# USB_OTG_HS.net
KiCad netlist of a schematic drawn in Altium Designer
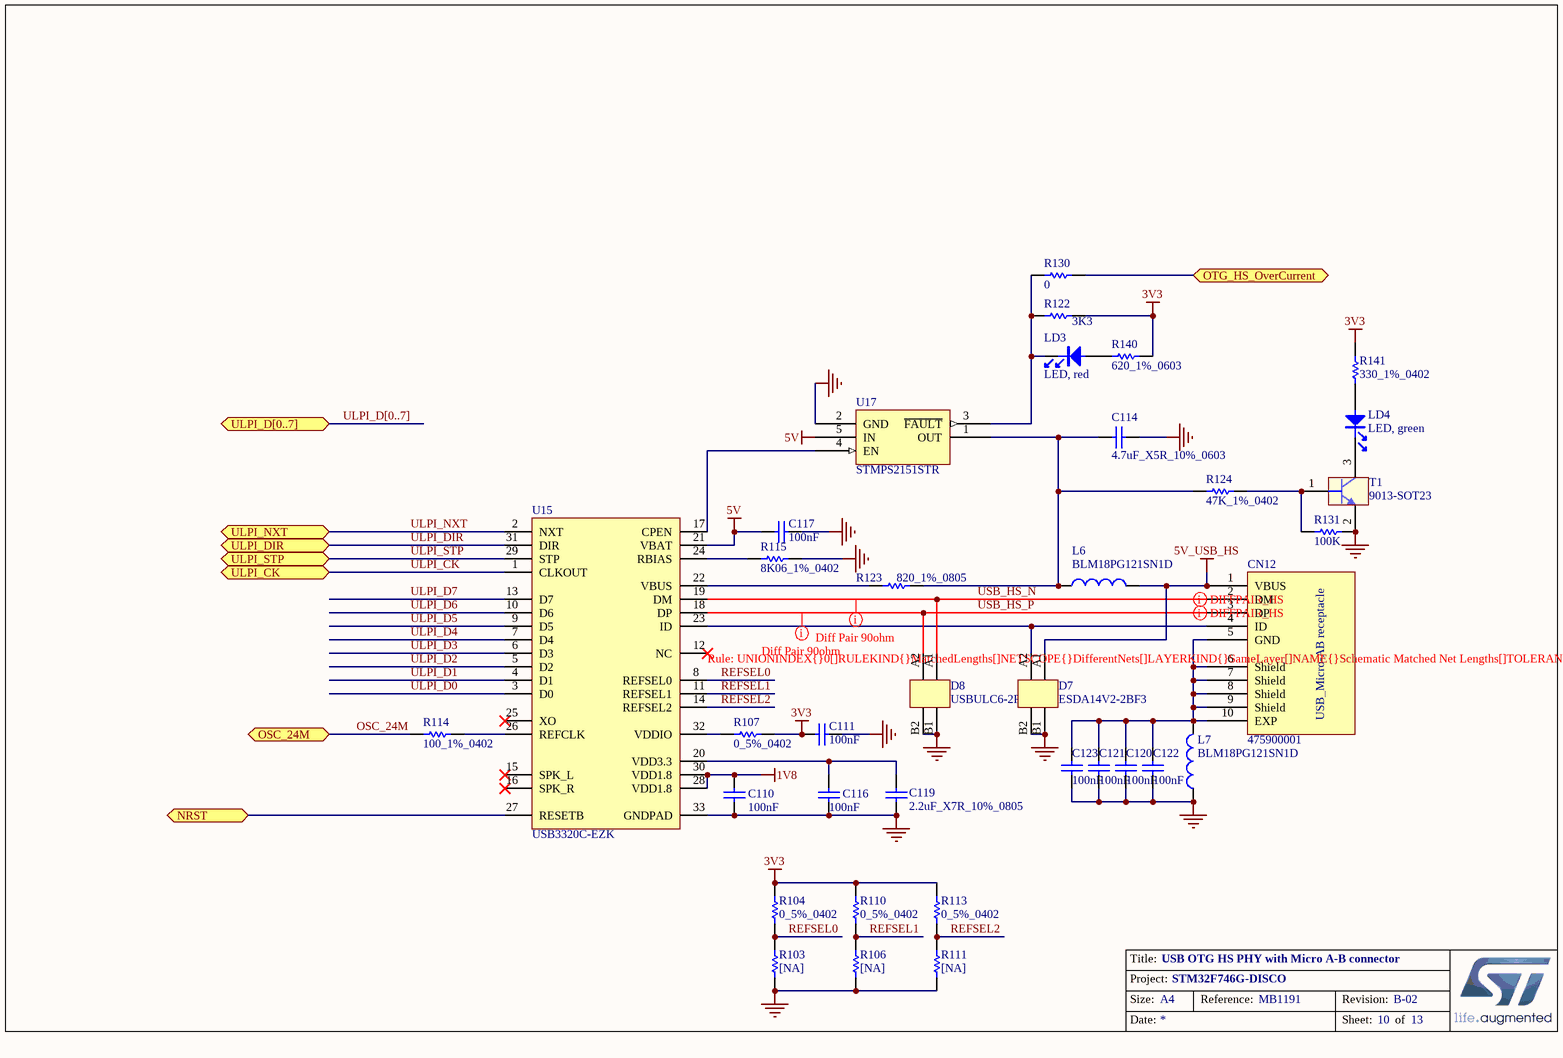
[diagram p0: USB_OTG_HS.SchDoc]

(export (version "E")
  (design (tool "Eeschema 10.0.6"))
  (components
    (comp (ref "C110")
      (value "100nF")
      (footprint "0402C")
      (description "Capacitor,100nF,16V,X7R,10%,0402,YAGEO")
      (libsource (lib "MCD_TOOLS") (part "Cap_100nF_X7R_10%_0402"))
    )
    (comp (ref "C111")
      (value "100nF")
      (footprint "0402C")
      (description "Capacitor,100nF,16V,X7R,10%,0402,YAGEO")
      (libsource (lib "MCD_TOOLS") (part "Cap_100nF_X7R_10%_0402"))
    )
    (comp (ref "C114")
      (value "4.7uF_X5R_10%_0603")
      (footprint "0603C")
      (description "Capacitor,4.7uF,16V, X5R,10%,0603,YAGEO")
      (libsource (lib "MCD_TOOLS") (part "Cap_4.7uF_X5R_10%_0603"))
    )
    (comp (ref "C116")
      (value "100nF")
      (footprint "0402C")
      (description "Capacitor,100nF,16V,X7R,10%,0402,YAGEO")
      (libsource (lib "MCD_TOOLS") (part "Cap_100nF_X7R_10%_0402"))
    )
    (comp (ref "C117")
      (value "100nF")
      (footprint "0402C")
      (description "Capacitor,100nF,16V,X7R,10%,0402,YAGEO")
      (libsource (lib "MCD_TOOLS") (part "Cap_100nF_X7R_10%_0402"))
    )
    (comp (ref "C119")
      (value "2.2uF_X7R_10%_0805")
      (footprint "TAN-A")
      (description "Capacitor,2.2uF,16V, X7R,10%,0805,YAGEO")
      (libsource (lib "MCD_TOOLS") (part "Cap_2.2uF_X7R_10%_0805"))
    )
    (comp (ref "C120")
      (value "100nF")
      (footprint "0402C")
      (description "Capacitor,100nF,16V,X7R,10%,0402,YAGEO")
      (libsource (lib "MCD_TOOLS") (part "Cap_100nF_X7R_10%_0402"))
    )
    (comp (ref "C121")
      (value "100nF")
      (footprint "0402C")
      (description "Capacitor,100nF,16V,X7R,10%,0402,YAGEO")
      (libsource (lib "MCD_TOOLS") (part "Cap_100nF_X7R_10%_0402"))
    )
    (comp (ref "C122")
      (value "100nF")
      (footprint "0402C")
      (description "Capacitor,100nF,16V,X7R,10%,0402,YAGEO")
      (libsource (lib "MCD_TOOLS") (part "Cap_100nF_X7R_10%_0402"))
    )
    (comp (ref "C123")
      (value "100nF")
      (footprint "0402C")
      (description "Capacitor,100nF,16V,X7R,10%,0402,YAGEO")
      (libsource (lib "MCD_TOOLS") (part "Cap_100nF_X7R_10%_0402"))
    )
    (comp (ref "CN12")
      (value "475900001")
      (footprint "USB-MICRO-AB")
      (description "USB-MICRO-AB, 47590-0001, SMT, MOLEX")
      (libsource (lib "MCD_TOOLS") (part "475900001"))
    )
    (comp (ref "D7")
      (value "ESDA14V2-2BF3")
      (footprint "BGA4_1X1")
      (description "Quad bidirectional Transil array for ESD protection")
      (libsource (lib "MCD_TOOLS") (part "ESDA14V2-2BF3"))
    )
    (comp (ref "D8")
      (value "USBULC6-2F3")
      (footprint "BGA4_1X1")
      (description "2-line Transil, (TVS), ultralow capacitance protection for high speed USB")
      (libsource (lib "MCD_TOOLS") (part "USBULC6-2F3"))
    )
    (comp (ref "L6")
      (value "BLM18PG121SN1D")
      (footprint "0603L")
      (description "Bead,120R,2A,0603,BLM18PG121SN1D,MURATA")
      (libsource (lib "MCD_TOOLS") (part "BEAD_120R_2A_0603"))
    )
    (comp (ref "L7")
      (value "BLM18PG121SN1D")
      (footprint "0603L")
      (description "Bead,120R,2A,0603,BLM18PG121SN1D,MURATA")
      (libsource (lib "MCD_TOOLS") (part "BEAD_120R_2A_0603"))
    )
    (comp (ref "LD3")
      (value "LED, red")
      (footprint "0603D")
      (description "LED,red,0603,19-213-R6C-AP1Q2B/3T,everlight")
      (libsource (lib "MCD_TOOLS") (part "LED_red"))
    )
    (comp (ref "LD4")
      (value "LED, green")
      (footprint "0603D")
      (description "LED,green,0603,19-213SYGC/S530-E2/TR8,everlight")
      (libsource (lib "MCD_TOOLS") (part "LED_green"))
    )
    (comp (ref "R103")
      (value "[NA]")
      (footprint "0402R")
      (description "Resistor,[NA],0402")
      (libsource (lib "MCD_TOOLS") (part "Res_NA_0402"))
    )
    (comp (ref "R104")
      (value "0_5%_0402")
      (footprint "0402R")
      (description "Resistor,0,0402,5%,YAGEO")
      (libsource (lib "MCD_TOOLS") (part "Res_0_5%_0402"))
    )
    (comp (ref "R106")
      (value "[NA]")
      (footprint "0402R")
      (description "Resistor,[NA],0402")
      (libsource (lib "MCD_TOOLS") (part "Res_NA_0402"))
    )
    (comp (ref "R107")
      (value "0_5%_0402")
      (footprint "0402R")
      (description "Resistor,0,0402,5%,YAGEO")
      (libsource (lib "MCD_TOOLS") (part "Res_0_5%_0402"))
    )
    (comp (ref "R110")
      (value "0_5%_0402")
      (footprint "0402R")
      (description "Resistor,0,0402,5%,YAGEO")
      (libsource (lib "MCD_TOOLS") (part "Res_0_5%_0402"))
    )
    (comp (ref "R111")
      (value "[NA]")
      (footprint "0402R")
      (description "Resistor,[NA],0402")
      (libsource (lib "MCD_TOOLS") (part "Res_NA_0402"))
    )
    (comp (ref "R113")
      (value "0_5%_0402")
      (footprint "0402R")
      (description "Resistor,0,0402,5%,YAGEO")
      (libsource (lib "MCD_TOOLS") (part "Res_0_5%_0402"))
    )
    (comp (ref "R114")
      (value "100_1%_0402")
      (footprint "0402R")
      (description "Resistor,100,0402,1%,YAGEO")
      (libsource (lib "MCD_TOOLS") (part "Res_100_1%_0402"))
    )
    (comp (ref "R115")
      (value "8K06_1%_0402")
      (footprint "0402R")
      (description "Resistor,8K06,0402,1%,YAGEO")
      (libsource (lib "MCD_TOOLS") (part "Res_8K06_1%_0402"))
    )
    (comp (ref "R122")
      (value "3K3")
      (footprint "0402R")
      (description "Resistor,3K3,0402,1%,YAGEO")
      (libsource (lib "MCD_TOOLS") (part "Res_3K3_1%_0402"))
    )
    (comp (ref "R123")
      (value "820_1%_0805")
      (footprint "0805R")
      (description "Resistor,820,0805,1%,YAGEO")
      (libsource (lib "MCD_TOOLS") (part "Res_820_1%_0805"))
    )
    (comp (ref "R124")
      (value "47K_1%_0402")
      (footprint "0402R")
      (description "Resistor,47K,0402,1%,YAGEO")
      (libsource (lib "MCD_TOOLS") (part "Res_47K_1%_0402"))
    )
    (comp (ref "R130")
      (value "0")
      (footprint "0402R")
      (description "Resistor,0,0402,5%,YAGEO")
      (libsource (lib "MCD_TOOLS") (part "Res_0_5%_0402"))
    )
    (comp (ref "R131")
      (value "100K")
      (footprint "0402R")
      (description "Resistor,100K,0402,1%,YAGEO")
      (libsource (lib "MCD_TOOLS") (part "Res_100K_1%_0402"))
    )
    (comp (ref "R140")
      (value "620_1%_0603")
      (footprint "0603R")
      (description "Resistor,620,0603,1%,VISHAY")
      (libsource (lib "MCD_TOOLS") (part "Res_620_1%_0603"))
    )
    (comp (ref "R141")
      (value "330_1%_0402")
      (footprint "0402R")
      (description "Resistor,330,0402,1%,YAGEO")
      (libsource (lib "MCD_TOOLS") (part "Res_330_1%_0402"))
    )
    (comp (ref "T1")
      (value "9013-SOT23")
      (footprint "SOT23")
      (description "NPN Bipolar Transistor, SOT-23 Footprint")
      (libsource (lib "MCD_TOOLS") (part "9013-SOT23"))
    )
    (comp (ref "U15")
      (value "USB3320C-EZK")
      (footprint "QFN32_0R5_5X5")
      (description "USB3320C, Hi-Speed USB Host, Device or OTG PHY with ULPI Low Pin Interface")
      (libsource (lib "MCD_TOOLS") (part "USB3320C-EZK"))
    )
    (comp (ref "U17")
      (value "STMPS2151STR")
      (footprint "SOT23-5L")
      (description "Enhanced single channel power switches")
      (libsource (lib "MCD_TOOLS") (part "STMPS2151STR"))
    )
  )
  (nets
    (net (code "1") (name "/NRST") (class "Default")
      (node (ref "U15") (pin "27") (pinfunction "RESETB_27") (pintype "passive"))
    )
    (net (code "2") (name "/OSC_24M") (class "Default")
      (node (ref "R114") (pin "1") (pinfunction "1_1") (pintype "passive"))
    )
    (net (code "3") (name "/OTG_HS_OverCurrent") (class "Default")
      (node (ref "R130") (pin "2") (pinfunction "2_2") (pintype "passive"))
    )
    (net (code "4") (name "/REFSEL0") (class "Default")
      (node (ref "R103") (pin "2") (pinfunction "2_2") (pintype "passive"))
      (node (ref "R104") (pin "1") (pinfunction "1_1") (pintype "passive"))
      (node (ref "U15") (pin "8") (pinfunction "REFSEL0_8") (pintype "passive"))
    )
    (net (code "5") (name "/REFSEL1") (class "Default")
      (node (ref "R106") (pin "2") (pinfunction "2_2") (pintype "passive"))
      (node (ref "R110") (pin "1") (pinfunction "1_1") (pintype "passive"))
      (node (ref "U15") (pin "11") (pinfunction "REFSEL1_11") (pintype "passive"))
    )
    (net (code "6") (name "/REFSEL2") (class "Default")
      (node (ref "R111") (pin "2") (pinfunction "2_2") (pintype "passive"))
      (node (ref "R113") (pin "1") (pinfunction "1_1") (pintype "passive"))
      (node (ref "U15") (pin "14") (pinfunction "REFSEL2_14") (pintype "passive"))
    )
    (net (code "7") (name "/ULPI_CK") (class "Default")
      (node (ref "U15") (pin "1") (pinfunction "CLKOUT_1") (pintype "passive"))
    )
    (net (code "8") (name "/ULPI_D0") (class "Default")
      (node (ref "U15") (pin "3") (pinfunction "D0_3") (pintype "passive"))
    )
    (net (code "9") (name "/ULPI_D1") (class "Default")
      (node (ref "U15") (pin "4") (pinfunction "D1_4") (pintype "passive"))
    )
    (net (code "10") (name "/ULPI_D2") (class "Default")
      (node (ref "U15") (pin "5") (pinfunction "D2_5") (pintype "passive"))
    )
    (net (code "11") (name "/ULPI_D3") (class "Default")
      (node (ref "U15") (pin "6") (pinfunction "D3_6") (pintype "passive"))
    )
    (net (code "12") (name "/ULPI_D4") (class "Default")
      (node (ref "U15") (pin "7") (pinfunction "D4_7") (pintype "passive"))
    )
    (net (code "13") (name "/ULPI_D5") (class "Default")
      (node (ref "U15") (pin "9") (pinfunction "D5_9") (pintype "passive"))
    )
    (net (code "14") (name "/ULPI_D6") (class "Default")
      (node (ref "U15") (pin "10") (pinfunction "D6_10") (pintype "passive"))
    )
    (net (code "15") (name "/ULPI_D7") (class "Default")
      (node (ref "U15") (pin "13") (pinfunction "D7_13") (pintype "passive"))
    )
    (net (code "16") (name "/ULPI_DIR") (class "Default")
      (node (ref "U15") (pin "31") (pinfunction "DIR_31") (pintype "passive"))
    )
    (net (code "18") (name "/ULPI_NXT") (class "Default")
      (node (ref "U15") (pin "2") (pinfunction "NXT_2") (pintype "passive"))
    )
    (net (code "19") (name "/ULPI_STP") (class "Default")
      (node (ref "U15") (pin "29") (pinfunction "STP_29") (pintype "passive"))
    )
    (net (code "20") (name "/USB_HS_N") (class "Default")
      (node (ref "CN12") (pin "2") (pinfunction "DM_2") (pintype "passive"))
      (node (ref "D8") (pin "A1") (pintype "passive"))
      (node (ref "U15") (pin "19") (pinfunction "DM_19") (pintype "passive"))
    )
    (net (code "21") (name "/USB_HS_P") (class "Default")
      (node (ref "CN12") (pin "3") (pinfunction "DP_3") (pintype "passive"))
      (node (ref "D8") (pin "A2") (pintype "passive"))
      (node (ref "U15") (pin "18") (pinfunction "DP_18") (pintype "passive"))
    )
    (net (code "22") (name "1V8") (class "Default")
      (node (ref "C110") (pin "2") (pinfunction "2_2") (pintype "passive"))
      (node (ref "U15") (pin "28") (pinfunction "VDD1.8_28") (pintype "passive"))
      (node (ref "U15") (pin "30") (pinfunction "VDD1.8_30") (pintype "passive"))
    )
    (net (code "23") (name "3V3") (class "Default")
      (node (ref "C111") (pin "1") (pinfunction "1_1") (pintype "passive"))
      (node (ref "R104") (pin "2") (pinfunction "2_2") (pintype "passive"))
      (node (ref "R107") (pin "2") (pinfunction "2_2") (pintype "passive"))
      (node (ref "R110") (pin "2") (pinfunction "2_2") (pintype "passive"))
      (node (ref "R113") (pin "2") (pinfunction "2_2") (pintype "passive"))
      (node (ref "R122") (pin "1") (pinfunction "1_1") (pintype "passive"))
      (node (ref "R140") (pin "2") (pinfunction "2_2") (pintype "passive"))
      (node (ref "R141") (pin "2") (pinfunction "2_2") (pintype "passive"))
    )
    (net (code "24") (name "5V") (class "Default")
      (node (ref "C117") (pin "1") (pinfunction "1_1") (pintype "passive"))
      (node (ref "U15") (pin "21") (pinfunction "VBAT_21") (pintype "passive"))
      (node (ref "U17") (pin "5") (pinfunction "IN_5") (pintype "passive"))
    )
    (net (code "25") (name "5V_USB_HS") (class "Default")
      (node (ref "CN12") (pin "1") (pinfunction "VBUS_1") (pintype "passive"))
      (node (ref "D7") (pin "A1") (pintype "passive"))
      (node (ref "L6") (pin "2") (pinfunction "2_2") (pintype "passive"))
    )
    (net (code "26") (name "GND") (class "Default")
      (node (ref "C110") (pin "1") (pinfunction "1_1") (pintype "passive"))
      (node (ref "C111") (pin "2") (pinfunction "2_2") (pintype "passive"))
      (node (ref "C114") (pin "2") (pinfunction "2_2") (pintype "passive"))
      (node (ref "C116") (pin "1") (pinfunction "1_1") (pintype "passive"))
      (node (ref "C117") (pin "2") (pinfunction "2_2") (pintype "passive"))
      (node (ref "C119") (pin "1") (pinfunction "1_1") (pintype "passive"))
      (node (ref "C120") (pin "1") (pinfunction "1_1") (pintype "passive"))
      (node (ref "C121") (pin "1") (pinfunction "1_1") (pintype "passive"))
      (node (ref "C122") (pin "1") (pinfunction "1_1") (pintype "passive"))
      (node (ref "C123") (pin "1") (pinfunction "1_1") (pintype "passive"))
      (node (ref "D7") (pin "B1") (pintype "passive"))
      (node (ref "D7") (pin "B2") (pintype "passive"))
      (node (ref "D8") (pin "B1") (pintype "passive"))
      (node (ref "D8") (pin "B2") (pintype "passive"))
      (node (ref "L7") (pin "1") (pinfunction "1_1") (pintype "passive"))
      (node (ref "R103") (pin "1") (pinfunction "1_1") (pintype "passive"))
      (node (ref "R106") (pin "1") (pinfunction "1_1") (pintype "passive"))
      (node (ref "R111") (pin "1") (pinfunction "1_1") (pintype "passive"))
      (node (ref "R115") (pin "2") (pinfunction "2_2") (pintype "passive"))
      (node (ref "R131") (pin "2") (pinfunction "2_2") (pintype "passive"))
      (node (ref "T1") (pin "2") (pinfunction "E_2") (pintype "passive"))
      (node (ref "U15") (pin "33") (pinfunction "GNDPAD_33") (pintype "passive"))
      (node (ref "U17") (pin "2") (pinfunction "GND_2") (pintype "passive"))
    )
    (net (code "27") (name "Net-(CN12-EXP)") (class "Default")
      (node (ref "C120") (pin "2") (pinfunction "2_2") (pintype "passive"))
      (node (ref "C121") (pin "2") (pinfunction "2_2") (pintype "passive"))
      (node (ref "C122") (pin "2") (pinfunction "2_2") (pintype "passive"))
      (node (ref "C123") (pin "2") (pinfunction "2_2") (pintype "passive"))
      (node (ref "CN12") (pin "10") (pinfunction "EXP_10") (pintype "passive"))
      (node (ref "CN12") (pin "5") (pinfunction "GND_5") (pintype "passive"))
      (node (ref "CN12") (pin "6") (pinfunction "Shield_6") (pintype "passive"))
      (node (ref "CN12") (pin "7") (pinfunction "Shield_7") (pintype "passive"))
      (node (ref "CN12") (pin "8") (pinfunction "Shield_8") (pintype "passive"))
      (node (ref "CN12") (pin "9") (pinfunction "Shield_9") (pintype "passive"))
      (node (ref "L7") (pin "2") (pinfunction "2_2") (pintype "passive"))
    )
    (net (code "28") (name "Net-(CN12-ID)") (class "Default")
      (node (ref "CN12") (pin "4") (pinfunction "ID_4") (pintype "passive"))
      (node (ref "D7") (pin "A2") (pintype "passive"))
      (node (ref "U15") (pin "23") (pinfunction "ID_23") (pintype "passive"))
    )
    (net (code "29") (name "Net-(LD3-Pad1)") (class "Default")
      (node (ref "LD3") (pin "1") (pintype "passive"))
      (node (ref "R140") (pin "1") (pinfunction "1_1") (pintype "passive"))
    )
    (net (code "30") (name "Net-(LD4-Pad1)") (class "Default")
      (node (ref "LD4") (pin "1") (pintype "passive"))
      (node (ref "R141") (pin "1") (pinfunction "1_1") (pintype "passive"))
    )
    (net (code "31") (name "Net-(T1-B)") (class "Default")
      (node (ref "R124") (pin "2") (pinfunction "2_2") (pintype "passive"))
      (node (ref "R131") (pin "1") (pinfunction "1_1") (pintype "passive"))
      (node (ref "T1") (pin "1") (pinfunction "B_1") (pintype "passive"))
    )
    (net (code "32") (name "Net-(T1-C)") (class "Default")
      (node (ref "LD4") (pin "2") (pintype "passive"))
      (node (ref "T1") (pin "3") (pinfunction "C_3") (pintype "passive"))
    )
    (net (code "33") (name "Net-(U15-CPEN)") (class "Default")
      (node (ref "U15") (pin "17") (pinfunction "CPEN_17") (pintype "passive"))
      (node (ref "U17") (pin "4") (pinfunction "EN_4") (pintype "input"))
    )
    (net (code "34") (name "Net-(U15-RBIAS)") (class "Default")
      (node (ref "R115") (pin "1") (pinfunction "1_1") (pintype "passive"))
      (node (ref "U15") (pin "24") (pinfunction "RBIAS_24") (pintype "passive"))
    )
    (net (code "35") (name "Net-(U15-REFCLK)") (class "Default")
      (node (ref "R114") (pin "2") (pinfunction "2_2") (pintype "passive"))
      (node (ref "U15") (pin "26") (pinfunction "REFCLK_26") (pintype "passive"))
    )
    (net (code "36") (name "Net-(U15-VBUS)") (class "Default")
      (node (ref "R123") (pin "1") (pinfunction "1_1") (pintype "passive"))
      (node (ref "U15") (pin "22") (pinfunction "VBUS_22") (pintype "passive"))
    )
    (net (code "37") (name "Net-(U15-VDD3.3)") (class "Default")
      (node (ref "C116") (pin "2") (pinfunction "2_2") (pintype "passive"))
      (node (ref "C119") (pin "2") (pinfunction "2_2") (pintype "passive"))
      (node (ref "U15") (pin "20") (pinfunction "VDD3.3_20") (pintype "passive"))
    )
    (net (code "38") (name "Net-(U15-VDDIO)") (class "Default")
      (node (ref "R107") (pin "1") (pinfunction "1_1") (pintype "passive"))
      (node (ref "U15") (pin "32") (pinfunction "VDDIO_32") (pintype "passive"))
    )
    (net (code "39") (name "Net-(U17-OUT)") (class "Default")
      (node (ref "C114") (pin "1") (pinfunction "1_1") (pintype "passive"))
      (node (ref "L6") (pin "1") (pinfunction "1_1") (pintype "passive"))
      (node (ref "R123") (pin "2") (pinfunction "2_2") (pintype "passive"))
      (node (ref "R124") (pin "1") (pinfunction "1_1") (pintype "passive"))
      (node (ref "U17") (pin "1") (pinfunction "OUT_1") (pintype "passive"))
    )
    (net (code "40") (name "Net-(U17-~{FAULT})") (class "Default")
      (node (ref "LD3") (pin "2") (pintype "passive"))
      (node (ref "R122") (pin "2") (pinfunction "2_2") (pintype "passive"))
      (node (ref "R130") (pin "1") (pinfunction "1_1") (pintype "passive"))
      (node (ref "U17") (pin "3") (pinfunction "~{FAULT}_3") (pintype "output"))
    )
    (net (code "41") (name "unconnected-(U15-NC-Pad12)") (class "Default")
      (node (ref "U15") (pin "12") (pinfunction "NC_12") (pintype "passive+no_connect"))
    )
    (net (code "42") (name "unconnected-(U15-SPK_L-Pad15)") (class "Default")
      (node (ref "U15") (pin "15") (pinfunction "SPK_L_15") (pintype "passive+no_connect"))
    )
    (net (code "43") (name "unconnected-(U15-SPK_R-Pad16)") (class "Default")
      (node (ref "U15") (pin "16") (pinfunction "SPK_R_16") (pintype "passive+no_connect"))
    )
    (net (code "44") (name "unconnected-(U15-XO-Pad25)") (class "Default")
      (node (ref "U15") (pin "25") (pinfunction "XO_25") (pintype "passive+no_connect"))
    )
  )
)
